# Schematic_nobuttons_noserial.net
KiCad netlist of a schematic drawn in EAGLE
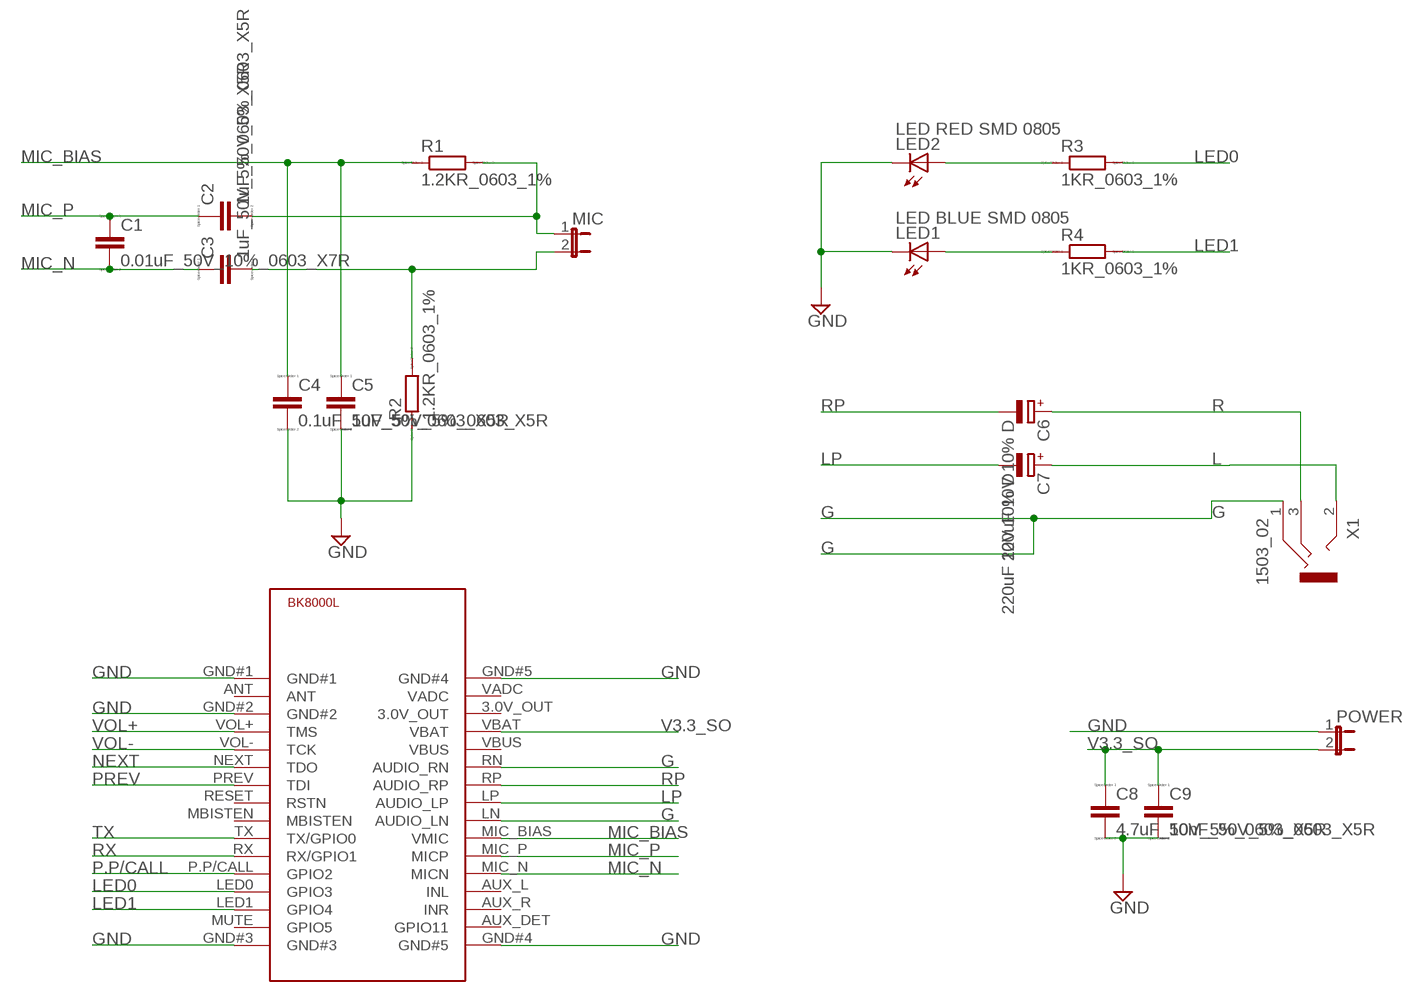
[diagram p0: schematic, sheet 1]

(export (version "E")
  (design (tool "Eeschema 10.0.6"))
  (components
    (comp (ref "C1")
      (value "0.01uF_50V_10%_0603_X7R")
      (footprint "eagle-import:C0603")
      (libsource (lib "eagle-import") (part "CC0603"))
    )
    (comp (ref "C2")
      (value "1uF_50V_5%_0603_X5R")
      (footprint "eagle-import:C0603")
      (libsource (lib "eagle-import") (part "CC0603"))
    )
    (comp (ref "C3")
      (value "1uF_50V_5%_0603_X5R")
      (footprint "eagle-import:C0603")
      (libsource (lib "eagle-import") (part "CC0603"))
    )
    (comp (ref "C4")
      (value "0.1uF_50V_5%_0603_X5R")
      (footprint "eagle-import:C0603")
      (libsource (lib "eagle-import") (part "CC0603"))
    )
    (comp (ref "C5")
      (value "1uF_50V_5%_0603_X5R")
      (footprint "eagle-import:C0603")
      (libsource (lib "eagle-import") (part "CC0603"))
    )
    (comp (ref "C6")
      (value "220uF 10V 10% D")
      (footprint "eagle-import:SMC_D")
      (libsource (lib "eagle-import") (part "CPOL-EUSMCD"))
    )
    (comp (ref "C7")
      (value "220uF 10V 10% D")
      (footprint "eagle-import:SMC_D")
      (libsource (lib "eagle-import") (part "CPOL-EUSMCD"))
    )
    (comp (ref "C8")
      (value "4.7uF_50V_5%_0603_X5R")
      (footprint "eagle-import:C0603")
      (libsource (lib "eagle-import") (part "CC0603"))
    )
    (comp (ref "C9")
      (value "10nF_50V_5%_0603_X5R")
      (footprint "eagle-import:C0603")
      (libsource (lib "eagle-import") (part "CC0603"))
    )
    (comp (ref "LED1")
      (value "LED BLUE SMD 0805")
      (footprint "eagle-import:CHIP-LED0805")
      (libsource (lib "eagle-import") (part "LEDCHIP-LED0805"))
    )
    (comp (ref "LED2")
      (value "LED RED SMD 0805")
      (footprint "eagle-import:CHIP-LED0805")
      (libsource (lib "eagle-import") (part "LEDCHIP-LED0805"))
    )
    (comp (ref "MIC")
      (value "JP1E")
      (footprint "eagle-import:JP1")
      (libsource (lib "eagle-import") (part "JP1E"))
    )
    (comp (ref "POWER")
      (value "JP1E")
      (footprint "eagle-import:JP1")
      (libsource (lib "eagle-import") (part "JP1E"))
    )
    (comp (ref "R1")
      (value "1.2KR_0603_1%")
      (footprint "eagle-import:R0603")
      (libsource (lib "eagle-import") (part "RR0603"))
    )
    (comp (ref "R2")
      (value "1.2KR_0603_1%")
      (footprint "eagle-import:R0603")
      (libsource (lib "eagle-import") (part "RR0603"))
    )
    (comp (ref "R3")
      (value "1KR_0603_1%")
      (footprint "eagle-import:R0603")
      (libsource (lib "eagle-import") (part "RR0603"))
    )
    (comp (ref "R4")
      (value "1KR_0603_1%")
      (footprint "eagle-import:R0603")
      (libsource (lib "eagle-import") (part "RR0603"))
    )
    (comp (ref "U$1")
      (value "BK8000LBK8000L_PAD")
      (footprint "eagle-import:BK8000L")
      (libsource (lib "eagle-import") (part "BK8000LBK8000L_PAD"))
    )
    (comp (ref "X1")
      (value "1503_02")
      (footprint "eagle-import:1503_02")
      (libsource (lib "eagle-import") (part "1503_02"))
    )
  )
  (nets
    (net (code "1") (name "/G") (class "Default")
      (node (ref "U$1") (pin "LN") (pinfunction "AUDIO_LN_LN") (pintype "bidirectional"))
      (node (ref "U$1") (pin "RN") (pinfunction "AUDIO_RN_RN") (pintype "bidirectional"))
      (node (ref "X1") (pin "1") (pinfunction "1_1") (pintype "passive"))
    )
    (net (code "2") (name "/L") (class "Default")
      (node (ref "C7") (pin "+") (pinfunction "+_+") (pintype "passive"))
      (node (ref "X1") (pin "2") (pinfunction "2_2") (pintype "passive"))
    )
    (net (code "3") (name "/LED0") (class "Default")
      (node (ref "R3") (pin "2") (pinfunction "2_2") (pintype "passive"))
      (node (ref "U$1") (pin "LED0") (pinfunction "GPIO3_LED0") (pintype "bidirectional"))
    )
    (net (code "4") (name "/LED1") (class "Default")
      (node (ref "R4") (pin "2") (pinfunction "2_2") (pintype "passive"))
      (node (ref "U$1") (pin "LED1") (pinfunction "GPIO4_LED1") (pintype "bidirectional"))
    )
    (net (code "5") (name "/LP") (class "Default")
      (node (ref "C7") (pin "-") (pinfunction "-_-") (pintype "passive"))
      (node (ref "U$1") (pin "LP") (pinfunction "AUDIO_LP_LP") (pintype "bidirectional"))
    )
    (net (code "6") (name "/MIC_BIAS") (class "Default")
      (node (ref "C4") (pin "1") (pinfunction "1_1") (pintype "passive"))
      (node (ref "C5") (pin "1") (pinfunction "1_1") (pintype "passive"))
      (node (ref "R1") (pin "1") (pinfunction "1_1") (pintype "passive"))
      (node (ref "U$1") (pin "MIC_BIAS") (pinfunction "VMIC_MIC_BIAS") (pintype "bidirectional"))
    )
    (net (code "7") (name "/MIC_N") (class "Default")
      (node (ref "C1") (pin "2") (pinfunction "2_2") (pintype "passive"))
      (node (ref "C3") (pin "1") (pinfunction "1_1") (pintype "passive"))
      (node (ref "U$1") (pin "MIC_N") (pinfunction "MICN_MIC_N") (pintype "bidirectional"))
    )
    (net (code "8") (name "/MIC_P") (class "Default")
      (node (ref "C1") (pin "1") (pinfunction "1_1") (pintype "passive"))
      (node (ref "C2") (pin "1") (pinfunction "1_1") (pintype "passive"))
      (node (ref "U$1") (pin "MIC_P") (pinfunction "MICP_MIC_P") (pintype "bidirectional"))
    )
    (net (code "9") (name "/NEXT") (class "Default")
      (node (ref "U$1") (pin "NEXT") (pinfunction "TDO_NEXT") (pintype "bidirectional"))
    )
    (net (code "10") (name "/P.P{slash}CALL") (class "Default")
      (node (ref "U$1") (pin "P.P/CALL") (pinfunction "GPIO2_P.P/CALL") (pintype "bidirectional"))
    )
    (net (code "11") (name "/PREV") (class "Default")
      (node (ref "U$1") (pin "PREV") (pinfunction "TDI_PREV") (pintype "bidirectional"))
    )
    (net (code "12") (name "/R") (class "Default")
      (node (ref "C6") (pin "+") (pinfunction "+_+") (pintype "passive"))
      (node (ref "X1") (pin "3") (pinfunction "3_3") (pintype "passive"))
    )
    (net (code "13") (name "/RP") (class "Default")
      (node (ref "C6") (pin "-") (pinfunction "-_-") (pintype "passive"))
      (node (ref "U$1") (pin "RP") (pinfunction "AUDIO_RP_RP") (pintype "bidirectional"))
    )
    (net (code "14") (name "/RX") (class "Default")
      (node (ref "U$1") (pin "RX") (pinfunction "RX/GPIO1_RX") (pintype "bidirectional"))
    )
    (net (code "15") (name "/TX") (class "Default")
      (node (ref "U$1") (pin "TX") (pinfunction "TX/GPIO0_TX") (pintype "bidirectional"))
    )
    (net (code "16") (name "/V3.3_SO") (class "Default")
      (node (ref "C8") (pin "1") (pinfunction "1_1") (pintype "passive"))
      (node (ref "C9") (pin "1") (pinfunction "1_1") (pintype "passive"))
      (node (ref "POWER") (pin "2") (pinfunction "2_2") (pintype "passive"))
      (node (ref "U$1") (pin "VBAT") (pinfunction "VBAT_VBAT") (pintype "bidirectional"))
    )
    (net (code "17") (name "/VOL+") (class "Default")
      (node (ref "U$1") (pin "VOL+") (pinfunction "TMS_VOL+") (pintype "bidirectional"))
    )
    (net (code "18") (name "/VOL-") (class "Default")
      (node (ref "U$1") (pin "VOL-") (pinfunction "TCK_VOL-") (pintype "bidirectional"))
    )
    (net (code "19") (name "GND") (class "Default")
      (node (ref "C4") (pin "2") (pinfunction "2_2") (pintype "passive"))
      (node (ref "C5") (pin "2") (pinfunction "2_2") (pintype "passive"))
      (node (ref "C8") (pin "2") (pinfunction "2_2") (pintype "passive"))
      (node (ref "C9") (pin "2") (pinfunction "2_2") (pintype "passive"))
      (node (ref "LED1") (pin "C") (pinfunction "C_C") (pintype "passive"))
      (node (ref "LED2") (pin "C") (pinfunction "C_C") (pintype "passive"))
      (node (ref "POWER") (pin "1") (pinfunction "1_1") (pintype "passive"))
      (node (ref "R2") (pin "1") (pinfunction "1_1") (pintype "passive"))
      (node (ref "U$1") (pin "GND#1") (pinfunction "GND#1_GND#1") (pintype "bidirectional"))
      (node (ref "U$1") (pin "GND#2") (pinfunction "GND#2_GND#2") (pintype "bidirectional"))
      (node (ref "U$1") (pin "GND#3") (pinfunction "GND#3_GND#3") (pintype "bidirectional"))
      (node (ref "U$1") (pin "GND#4") (pinfunction "GND#5_GND#4") (pintype "bidirectional"))
      (node (ref "U$1") (pin "GND#5") (pinfunction "GND#4_GND#5") (pintype "bidirectional"))
    )
    (net (code "20") (name "Net-(C2-Pad2)") (class "Default")
      (node (ref "C2") (pin "2") (pinfunction "2_2") (pintype "passive"))
      (node (ref "MIC") (pin "1") (pinfunction "1_1") (pintype "passive"))
      (node (ref "R1") (pin "2") (pinfunction "2_2") (pintype "passive"))
    )
    (net (code "21") (name "Net-(C3-Pad2)") (class "Default")
      (node (ref "C3") (pin "2") (pinfunction "2_2") (pintype "passive"))
      (node (ref "MIC") (pin "2") (pinfunction "2_2") (pintype "passive"))
      (node (ref "R2") (pin "2") (pinfunction "2_2") (pintype "passive"))
    )
    (net (code "22") (name "Net-(LED1-PadA)") (class "Default")
      (node (ref "LED1") (pin "A") (pinfunction "A_A") (pintype "passive"))
      (node (ref "R4") (pin "1") (pinfunction "1_1") (pintype "passive"))
    )
    (net (code "23") (name "Net-(LED2-PadA)") (class "Default")
      (node (ref "LED2") (pin "A") (pinfunction "A_A") (pintype "passive"))
      (node (ref "R3") (pin "1") (pinfunction "1_1") (pintype "passive"))
    )
    (net (code "24") (name "unconnected-(U$1-GPIO5-PadMUTE)") (class "Default")
      (node (ref "U$1") (pin "MUTE") (pinfunction "GPIO5_MUTE") (pintype "bidirectional"))
    )
    (net (code "25") (name "unconnected-(U$1-GPIO11-PadAUX_DET)") (class "Default")
      (node (ref "U$1") (pin "AUX_DET") (pinfunction "GPIO11_AUX_DET") (pintype "bidirectional"))
    )
    (net (code "26") (name "unconnected-(U$1-INL-PadAUX_L)") (class "Default")
      (node (ref "U$1") (pin "AUX_L") (pinfunction "INL_AUX_L") (pintype "bidirectional"))
    )
    (net (code "27") (name "unconnected-(U$1-INR-PadAUX_R)") (class "Default")
      (node (ref "U$1") (pin "AUX_R") (pinfunction "INR_AUX_R") (pintype "bidirectional"))
    )
    (net (code "28") (name "unconnected-(U$1-Pad3.0V_OUT)") (class "Default")
      (node (ref "U$1") (pin "3.0V_OUT") (pinfunction "3.0V_OUT_3.0V_OUT") (pintype "bidirectional"))
    )
    (net (code "29") (name "unconnected-(U$1-PadANT)") (class "Default")
      (node (ref "U$1") (pin "ANT") (pinfunction "ANT_ANT") (pintype "bidirectional"))
    )
    (net (code "30") (name "unconnected-(U$1-PadMBISTEN)") (class "Default")
      (node (ref "U$1") (pin "MBISTEN") (pinfunction "MBISTEN_MBISTEN") (pintype "bidirectional"))
    )
    (net (code "31") (name "unconnected-(U$1-PadVADC)") (class "Default")
      (node (ref "U$1") (pin "VADC") (pinfunction "VADC_VADC") (pintype "bidirectional"))
    )
    (net (code "32") (name "unconnected-(U$1-PadVBUS)") (class "Default")
      (node (ref "U$1") (pin "VBUS") (pinfunction "VBUS_VBUS") (pintype "bidirectional"))
    )
    (net (code "33") (name "unconnected-(U$1-RSTN-PadRESET)") (class "Default")
      (node (ref "U$1") (pin "RESET") (pinfunction "RSTN_RESET") (pintype "bidirectional"))
    )
    (net (code "34") (name "unconnected-(X1-2-Pad2@2)") (class "Default")
      (node (ref "X1") (pin "2@2") (pinfunction "2_2@2") (pintype "passive"))
    )
  )
)
